# HV_Indicator.net
KiCad netlist of a schematic drawn in Altium Designer
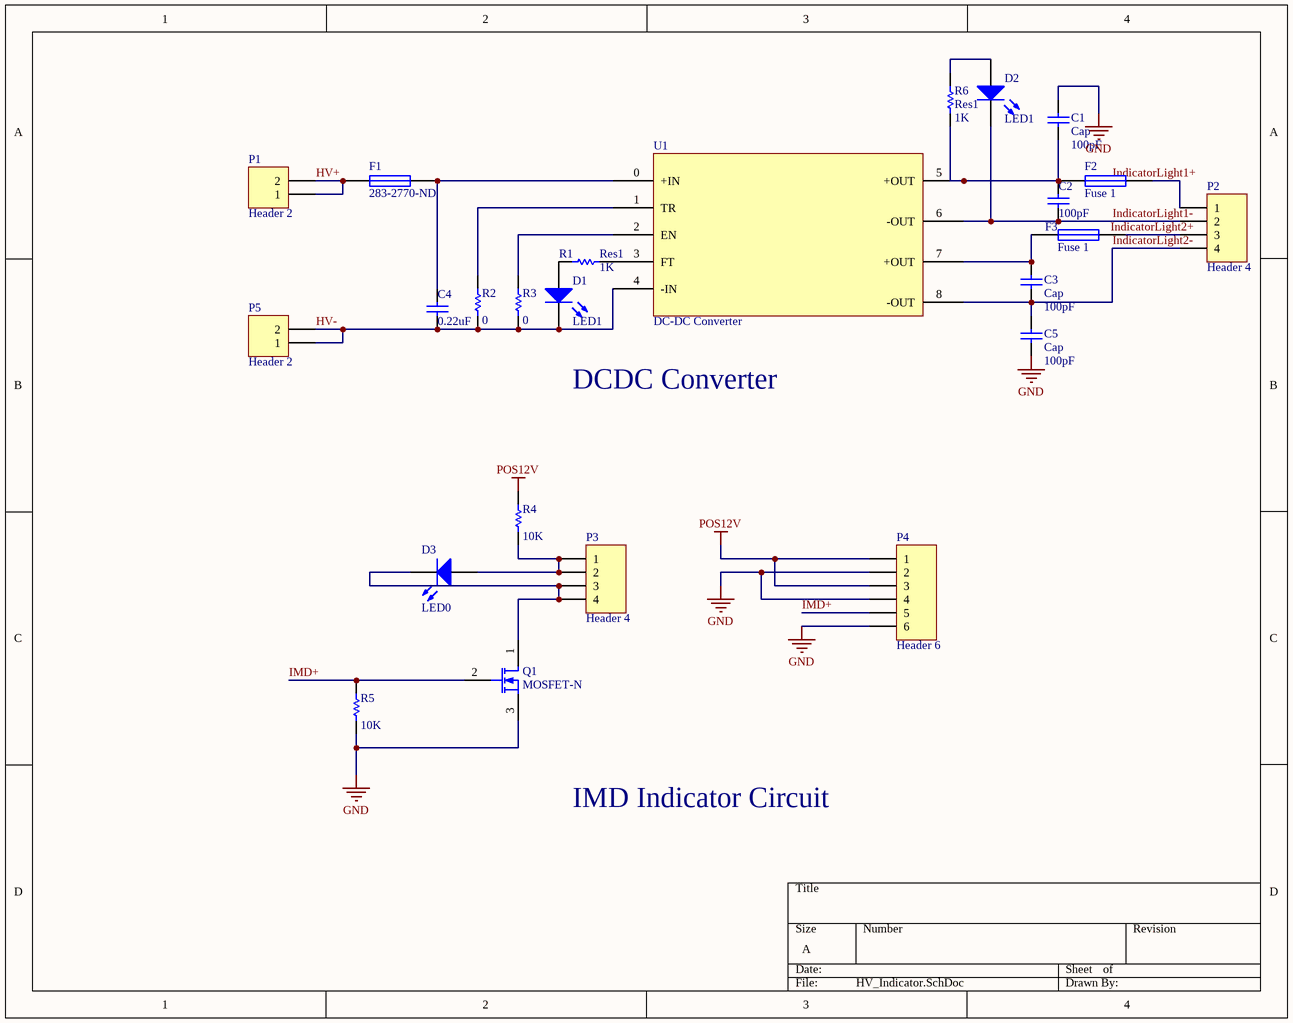
[diagram p0: HV_Indicator.SchDoc]

(export (version "E")
  (design (tool "Eeschema 10.0.6"))
  (components
    (comp (ref "C1")
      (value "Cap")
      (footprint "1206")
      (description "Capacitor")
      (fields (field (name "ALTIUM_VALUE") "100pF") (field (name "PUBLISHER") "Altium Limited"))
      (libsource (lib "Miscellaneous Devices") (part "Cap"))
    )
    (comp (ref "C2")
      (value "100pF")
      (footprint "1206")
      (description "Capacitor")
      (fields (field (name "Comment") "Cap") (field (name "PUBLISHER") "Altium Limited"))
      (libsource (lib "Miscellaneous Devices") (part "Cap"))
    )
    (comp (ref "C3")
      (value "Cap")
      (footprint "1206")
      (description "Capacitor")
      (fields (field (name "ALTIUM_VALUE") "100pF") (field (name "PUBLISHER") "Altium Limited"))
      (libsource (lib "Miscellaneous Devices") (part "Cap"))
    )
    (comp (ref "C4")
      (value "0.22uF")
      (footprint "RAD-0.3")
      (description "Capacitor")
      (fields (field (name "Comment") "Cap") (field (name "PUBLISHER") "Altium Limited"))
      (libsource (lib "Miscellaneous Devices") (part "Cap"))
    )
    (comp (ref "C5")
      (value "Cap")
      (footprint "1206")
      (description "Capacitor")
      (fields (field (name "ALTIUM_VALUE") "100pF") (field (name "PUBLISHER") "Altium Limited"))
      (libsource (lib "Miscellaneous Devices") (part "Cap"))
    )
    (comp (ref "D1")
      (value "LED1")
      (footprint "1206 DIODE")
      (description "Typical RED GaAs LED")
      (fields (field (name "PUBLISHER") "Altium Limited"))
      (libsource (lib "Miscellaneous Devices") (part "LED1"))
    )
    (comp (ref "D2")
      (value "LED1")
      (footprint "1206 DIODE")
      (description "Typical RED GaAs LED")
      (fields (field (name "PUBLISHER") "Altium Limited"))
      (libsource (lib "Miscellaneous Devices") (part "LED1"))
    )
    (comp (ref "D3")
      (value "LED0")
      (footprint "1206 LED")
      (description "Typical INFRARED GaAs LED")
      (fields (field (name "PUBLISHER") "Altium Limited"))
      (libsource (lib "Miscellaneous Devices") (part "LED0"))
    )
    (comp (ref "F1")
      (value "283-2770-ND")
      (footprint "RAD-0.2")
      (description "Fuse")
      (fields (field (name "PUBLISHER") "Altium Limited"))
      (libsource (lib "Miscellaneous Devices") (part "Fuse 1"))
    )
    (comp (ref "F2")
      (value "Fuse 1")
      (footprint "FuseHolder")
      (description "Fuse")
      (fields (field (name "PUBLISHER") "Altium Limited"))
      (libsource (lib "Miscellaneous Devices") (part "Fuse 1"))
    )
    (comp (ref "F3")
      (value "Fuse 1")
      (footprint "FuseHolder")
      (description "Fuse")
      (fields (field (name "PUBLISHER") "Altium Limited"))
      (libsource (lib "Miscellaneous Devices") (part "Fuse 1"))
    )
    (comp (ref "P1")
      (value "Header 2")
      (footprint "2POS TERM BLOCK")
      (description "Header, 2-Pin")
      (fields (field (name "PUBLISHER") "Altium Limited"))
      (libsource (lib "Miscellaneous Connectors") (part "Header 2"))
    )
    (comp (ref "P2")
      (value "Header 4")
      (footprint "4POS TERM BLOCK")
      (description "Header, 4-Pin")
      (fields (field (name "PUBLISHER") "Altium Limited"))
      (libsource (lib "Miscellaneous Connectors") (part "Header 4"))
    )
    (comp (ref "P3")
      (value "Header 4")
      (footprint "4POS TERM BLOCK")
      (description "Header, 4-Pin")
      (fields (field (name "PUBLISHER") "Altium Limited"))
      (libsource (lib "Miscellaneous Connectors") (part "Header 4"))
    )
    (comp (ref "P4")
      (value "Header 6")
      (footprint "6POS TERM BLOCK")
      (description "Header, 6-Pin")
      (fields (field (name "PUBLISHER") "Altium Limited"))
      (libsource (lib "Miscellaneous Connectors") (part "Header 6"))
    )
    (comp (ref "P5")
      (value "Header 2")
      (footprint "2POS TERM BLOCK")
      (description "Header, 2-Pin")
      (fields (field (name "PUBLISHER") "Altium Limited"))
      (libsource (lib "Miscellaneous Connectors") (part "Header 2"))
    )
    (comp (ref "Q1")
      (value "MOSFET-N")
      (footprint "SOT-23-3")
      (description "N-Channel MOSFET")
      (fields (field (name "PUBLISHER") "Altium Limited"))
      (libsource (lib "Miscellaneous Devices") (part "MOSFET-N"))
    )
    (comp (ref "R1")
      (value "Res1")
      (footprint "1206")
      (description "Resistor")
      (fields (field (name "ALTIUM_VALUE") "1K") (field (name "PUBLISHER") "Altium Limited"))
      (libsource (lib "Miscellaneous Devices") (part "Res1"))
    )
    (comp (ref "R2")
      (value "0")
      (footprint "1206")
      (description "Resistor")
      (fields (field (name "Comment") "Res1") (field (name "PUBLISHER") "Altium Limited"))
      (libsource (lib "Miscellaneous Devices") (part "Res1"))
    )
    (comp (ref "R3")
      (value "0")
      (footprint "1206")
      (description "Resistor")
      (fields (field (name "Comment") "Res1") (field (name "PUBLISHER") "Altium Limited"))
      (libsource (lib "Miscellaneous Devices") (part "Res1"))
    )
    (comp (ref "R4")
      (value "10K")
      (footprint "1206")
      (description "Resistor")
      (fields (field (name "Comment") "Res1") (field (name "PUBLISHER") "Altium Limited"))
      (libsource (lib "Miscellaneous Devices") (part "Res1"))
    )
    (comp (ref "R5")
      (value "10K")
      (footprint "1206")
      (description "Resistor")
      (fields (field (name "Comment") "Res1") (field (name "PUBLISHER") "Altium Limited"))
      (libsource (lib "Miscellaneous Devices") (part "Res1"))
    )
    (comp (ref "R6")
      (value "Res1")
      (footprint "1206")
      (description "Resistor")
      (fields (field (name "ALTIUM_VALUE") "1K") (field (name "PUBLISHER") "Altium Limited"))
      (libsource (lib "Miscellaneous Devices") (part "Res1"))
    )
    (comp (ref "U1")
      (value "DC-DC Converter")
      (footprint "DCM290y138x600A40")
      (libsource (lib "ic") (part "DC-DC Converter"))
    )
  )
  (nets
    (net (code "1") (name "/HV+") (class "Default")
      (node (ref "F1") (pin "1") (pinfunction "1_1") (pintype "passive"))
      (node (ref "P1") (pin "1") (pinfunction "1_1") (pintype "passive"))
      (node (ref "P1") (pin "2") (pinfunction "2_2") (pintype "passive"))
    )
    (net (code "2") (name "/HV-") (class "Default")
      (node (ref "C4") (pin "1") (pinfunction "1_1") (pintype "passive"))
      (node (ref "D1") (pin "2") (pinfunction "K_2") (pintype "passive"))
      (node (ref "P5") (pin "1") (pinfunction "1_1") (pintype "passive"))
      (node (ref "P5") (pin "2") (pinfunction "2_2") (pintype "passive"))
      (node (ref "R2") (pin "1") (pinfunction "1_1") (pintype "passive"))
      (node (ref "R3") (pin "1") (pinfunction "1_1") (pintype "passive"))
      (node (ref "U1") (pin "4") (pinfunction "-IN_4") (pintype "passive"))
    )
    (net (code "3") (name "/IMD+") (class "Default")
      (node (ref "P4") (pin "5") (pinfunction "5_5") (pintype "passive"))
      (node (ref "Q1") (pin "2") (pinfunction "G_2") (pintype "passive"))
      (node (ref "R5") (pin "2") (pinfunction "2_2") (pintype "passive"))
    )
    (net (code "5") (name "/IndicatorLight1-") (class "Default")
      (node (ref "C2") (pin "1") (pinfunction "1_1") (pintype "passive"))
      (node (ref "D2") (pin "2") (pinfunction "K_2") (pintype "passive"))
      (node (ref "P2") (pin "2") (pinfunction "2_2") (pintype "passive"))
      (node (ref "U1") (pin "6") (pinfunction "-OUT_6") (pintype "passive"))
    )
    (net (code "7") (name "/IndicatorLight2-") (class "Default")
      (node (ref "C3") (pin "1") (pinfunction "1_1") (pintype "passive"))
      (node (ref "C5") (pin "2") (pinfunction "2_2") (pintype "passive"))
      (node (ref "P2") (pin "4") (pinfunction "4_4") (pintype "passive"))
      (node (ref "U1") (pin "8") (pinfunction "-OUT_8") (pintype "passive"))
    )
    (net (code "8") (name "GND") (class "Default")
      (node (ref "C1") (pin "2") (pinfunction "2_2") (pintype "passive"))
      (node (ref "C5") (pin "1") (pinfunction "1_1") (pintype "passive"))
      (node (ref "P4") (pin "2") (pinfunction "2_2") (pintype "passive"))
      (node (ref "P4") (pin "4") (pinfunction "4_4") (pintype "passive"))
      (node (ref "P4") (pin "6") (pinfunction "6_6") (pintype "passive"))
      (node (ref "Q1") (pin "3") (pinfunction "S_3") (pintype "passive"))
      (node (ref "R5") (pin "1") (pinfunction "1_1") (pintype "passive"))
    )
    (net (code "9") (name "Net-(C1-Pad1)") (class "Default")
      (node (ref "C1") (pin "1") (pinfunction "1_1") (pintype "passive"))
      (node (ref "C2") (pin "2") (pinfunction "2_2") (pintype "passive"))
      (node (ref "F2") (pin "1") (pinfunction "1_1") (pintype "passive"))
      (node (ref "R6") (pin "1") (pinfunction "1_1") (pintype "passive"))
      (node (ref "U1") (pin "5") (pinfunction "+OUT_5") (pintype "passive"))
    )
    (net (code "10") (name "Net-(C3-Pad2)") (class "Default")
      (node (ref "C3") (pin "2") (pinfunction "2_2") (pintype "passive"))
      (node (ref "F3") (pin "1") (pinfunction "1_1") (pintype "passive"))
      (node (ref "U1") (pin "7") (pinfunction "+OUT_7") (pintype "passive"))
    )
    (net (code "11") (name "Net-(D1-A)") (class "Default")
      (node (ref "D1") (pin "1") (pinfunction "A_1") (pintype "passive"))
      (node (ref "R1") (pin "2") (pinfunction "2_2") (pintype "passive"))
    )
    (net (code "12") (name "Net-(D2-A)") (class "Default")
      (node (ref "D2") (pin "1") (pinfunction "A_1") (pintype "passive"))
      (node (ref "R6") (pin "2") (pinfunction "2_2") (pintype "passive"))
    )
    (net (code "13") (name "Net-(D3-A)") (class "Default")
      (node (ref "D3") (pin "1") (pinfunction "A_1") (pintype "passive"))
      (node (ref "P3") (pin "1") (pinfunction "1_1") (pintype "passive"))
      (node (ref "P3") (pin "2") (pinfunction "2_2") (pintype "passive"))
      (node (ref "R4") (pin "1") (pinfunction "1_1") (pintype "passive"))
    )
    (net (code "14") (name "Net-(D3-K)") (class "Default")
      (node (ref "D3") (pin "2") (pinfunction "K_2") (pintype "passive"))
      (node (ref "P3") (pin "3") (pinfunction "3_3") (pintype "passive"))
      (node (ref "P3") (pin "4") (pinfunction "4_4") (pintype "passive"))
      (node (ref "Q1") (pin "1") (pinfunction "D_1") (pintype "passive"))
    )
    (net (code "15") (name "Net-(F2-Pad2)") (class "Default")
      (node (ref "F2") (pin "2") (pinfunction "2_2") (pintype "passive"))
      (node (ref "P2") (pin "1") (pinfunction "1_1") (pintype "passive"))
    )
    (net (code "16") (name "Net-(F3-Pad2)") (class "Default")
      (node (ref "F3") (pin "2") (pinfunction "2_2") (pintype "passive"))
      (node (ref "P2") (pin "3") (pinfunction "3_3") (pintype "passive"))
    )
    (net (code "17") (name "Net-(U1-+IN)") (class "Default")
      (node (ref "C4") (pin "2") (pinfunction "2_2") (pintype "passive"))
      (node (ref "F1") (pin "2") (pinfunction "2_2") (pintype "passive"))
      (node (ref "U1") (pin "0") (pinfunction "+IN_0") (pintype "passive"))
    )
    (net (code "18") (name "Net-(U1-EN)") (class "Default")
      (node (ref "R3") (pin "2") (pinfunction "2_2") (pintype "passive"))
      (node (ref "U1") (pin "2") (pinfunction "EN_2") (pintype "passive"))
    )
    (net (code "19") (name "Net-(U1-FT)") (class "Default")
      (node (ref "R1") (pin "1") (pinfunction "1_1") (pintype "passive"))
      (node (ref "U1") (pin "3") (pinfunction "FT_3") (pintype "passive"))
    )
    (net (code "20") (name "Net-(U1-TR)") (class "Default")
      (node (ref "R2") (pin "2") (pinfunction "2_2") (pintype "passive"))
      (node (ref "U1") (pin "1") (pinfunction "TR_1") (pintype "passive"))
    )
    (net (code "21") (name "POS12V") (class "Default")
      (node (ref "P4") (pin "1") (pinfunction "1_1") (pintype "passive"))
      (node (ref "P4") (pin "3") (pinfunction "3_3") (pintype "passive"))
      (node (ref "R4") (pin "2") (pinfunction "2_2") (pintype "passive"))
    )
  )
)
